# SUPPLY.net
KiCad netlist of a schematic drawn in Altium Designer
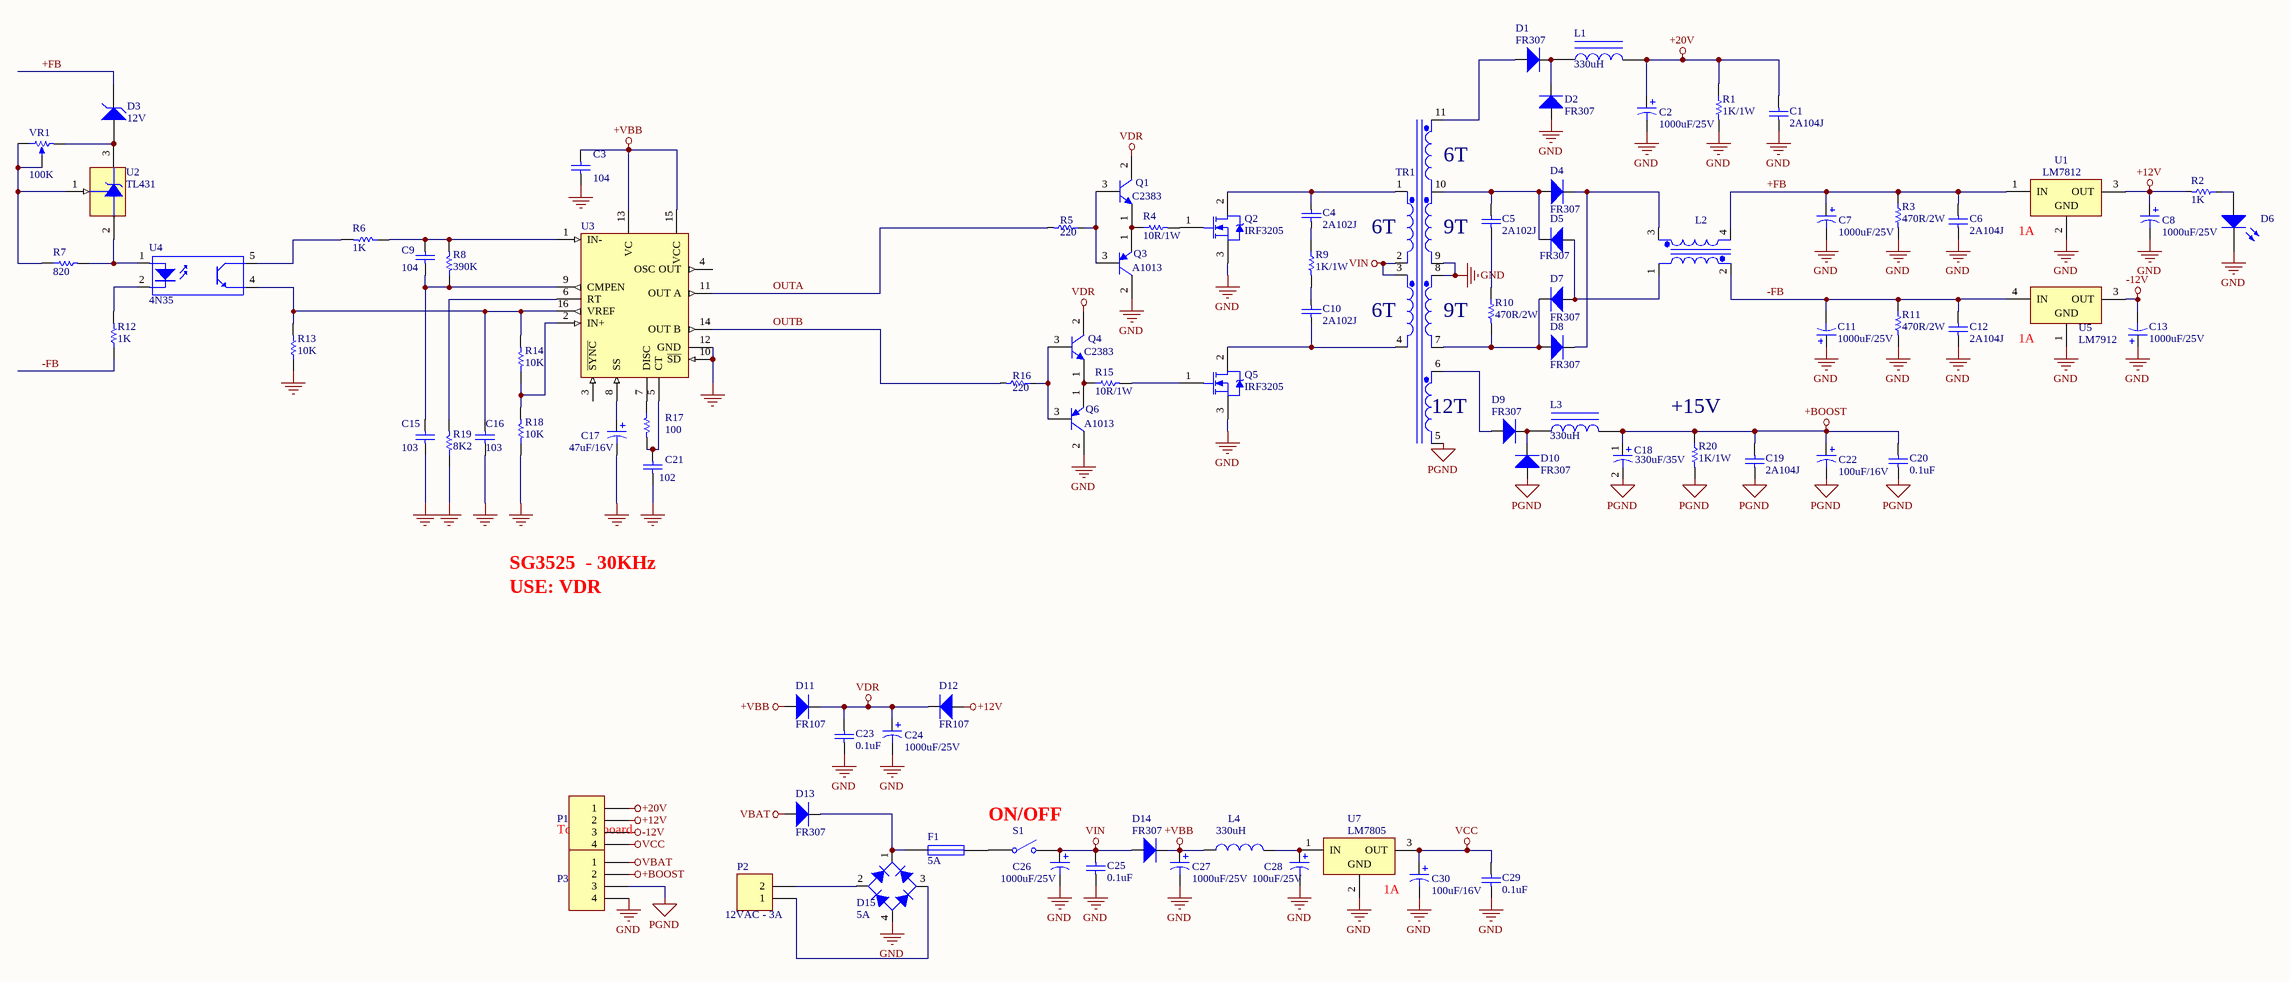
[diagram p0: SUPPLY.SchDoc]

(export (version "E")
  (design (tool "Eeschema 10.0.6"))
  (components
    (comp (ref "C1")
      (value "2A104J")
      (footprint "CAP2/3")
      (description "Capacitor")
      (fields (field (name "PUBLISHER") "Altium Limited"))
      (libsource (lib "Miscellaneous Devices") (part "Cap"))
    )
    (comp (ref "C2")
      (value "1000uF/25V")
      (footprint "C-400")
      (description "Polarized Capacitor (Radial)")
      (fields (field (name "PUBLISHER") "Altium Limited"))
      (libsource (lib "Miscellaneous Devices") (part "Cap Pol1"))
    )
    (comp (ref "C3")
      (value "104")
      (footprint "C1206")
      (description "Capacitor")
      (fields (field (name "PUBLISHER") "Altium Limited"))
      (libsource (lib "Miscellaneous Devices") (part "Cap"))
    )
    (comp (ref "C4")
      (value "2A102J")
      (footprint "CAP200")
      (description "Capacitor")
      (fields (field (name "PUBLISHER") "Altium Limited"))
      (libsource (lib "") (part "Cap_1"))
    )
    (comp (ref "C5")
      (value "2A102J")
      (footprint "CAP200")
      (description "Capacitor")
      (fields (field (name "PUBLISHER") "Altium Limited"))
      (libsource (lib "Miscellaneous Devices") (part "Cap"))
    )
    (comp (ref "C6")
      (value "2A104J")
      (footprint "CAP2/3")
      (description "Capacitor")
      (fields (field (name "PUBLISHER") "Altium Limited"))
      (libsource (lib "Miscellaneous Devices") (part "Cap"))
    )
    (comp (ref "C7")
      (value "1000uF/25V")
      (footprint "C-400")
      (description "Polarized Capacitor (Radial)")
      (fields (field (name "PUBLISHER") "Altium Limited"))
      (libsource (lib "Miscellaneous Devices") (part "Cap Pol1"))
    )
    (comp (ref "C8")
      (value "1000uF/25V")
      (footprint "C-400")
      (description "Polarized Capacitor (Radial)")
      (fields (field (name "PUBLISHER") "Altium Limited"))
      (libsource (lib "Miscellaneous Devices") (part "Cap Pol1"))
    )
    (comp (ref "C9")
      (value "104")
      (footprint "C1206")
      (description "Capacitor")
      (fields (field (name "PUBLISHER") "Altium Limited"))
      (libsource (lib "Miscellaneous Devices") (part "Cap"))
    )
    (comp (ref "C10")
      (value "2A102J")
      (footprint "CAP200")
      (description "Capacitor")
      (fields (field (name "PUBLISHER") "Altium Limited"))
      (libsource (lib "") (part "Cap_1"))
    )
    (comp (ref "C11")
      (value "1000uF/25V")
      (footprint "C-400")
      (description "Polarized Capacitor (Radial)")
      (fields (field (name "PUBLISHER") "Altium Limited"))
      (libsource (lib "Miscellaneous Devices") (part "Cap Pol1"))
    )
    (comp (ref "C12")
      (value "2A104J")
      (footprint "CAP2/3")
      (description "Capacitor")
      (fields (field (name "PUBLISHER") "Altium Limited"))
      (libsource (lib "Miscellaneous Devices") (part "Cap"))
    )
    (comp (ref "C13")
      (value "1000uF/25V")
      (footprint "C-400")
      (description "Polarized Capacitor (Radial)")
      (fields (field (name "PUBLISHER") "Altium Limited"))
      (libsource (lib "Miscellaneous Devices") (part "Cap Pol1"))
    )
    (comp (ref "C15")
      (value "103")
      (footprint "C0805")
      (description "Capacitor")
      (fields (field (name "PUBLISHER") "Altium Limited"))
      (libsource (lib "Miscellaneous Devices") (part "Cap"))
    )
    (comp (ref "C16")
      (value "103")
      (footprint "C0805")
      (description "Capacitor")
      (fields (field (name "PUBLISHER") "Altium Limited"))
      (libsource (lib "Miscellaneous Devices") (part "Cap"))
    )
    (comp (ref "C17")
      (value "47uF/16V")
      (footprint "C107-SMD")
      (description "Polarized Capacitor (Radial)")
      (fields (field (name "PUBLISHER") "Altium Limited"))
      (libsource (lib "Miscellaneous Devices") (part "Cap Pol1"))
    )
    (comp (ref "C18")
      (value "330uF/35V")
      (footprint "CAP-100UF/63V")
      (description "Polarized Capacitor (Radial)")
      (fields (field (name "PUBLISHER") "Altium Limited"))
      (libsource (lib "") (part "Cap Pol1_1"))
    )
    (comp (ref "C19")
      (value "2A104J")
      (footprint "CAP2/3")
      (description "Capacitor")
      (fields (field (name "PUBLISHER") "Altium Limited"))
      (libsource (lib "Miscellaneous Devices") (part "Cap"))
    )
    (comp (ref "C20")
      (value "0.1uF")
      (footprint "C1206")
      (description "Capacitor")
      (fields (field (name "PUBLISHER") "Altium Limited"))
      (libsource (lib "Miscellaneous Devices") (part "Cap"))
    )
    (comp (ref "C21")
      (value "102")
      (footprint "C0805")
      (description "Capacitor")
      (fields (field (name "PUBLISHER") "Altium Limited"))
      (libsource (lib "Miscellaneous Devices") (part "Cap"))
    )
    (comp (ref "C22")
      (value "100uF/16V")
      (footprint "CAP-100UF/16V")
      (description "Polarized Capacitor (Radial)")
      (fields (field (name "PUBLISHER") "Altium Limited"))
      (libsource (lib "Miscellaneous Devices") (part "Cap Pol1"))
    )
    (comp (ref "C23")
      (value "0.1uF")
      (footprint "C1206")
      (description "Capacitor")
      (fields (field (name "PUBLISHER") "Altium Limited"))
      (libsource (lib "Miscellaneous Devices") (part "Cap"))
    )
    (comp (ref "C24")
      (value "1000uF/25V")
      (footprint "C-400")
      (description "Polarized Capacitor (Radial)")
      (fields (field (name "PUBLISHER") "Altium Limited"))
      (libsource (lib "Miscellaneous Devices") (part "Cap Pol1"))
    )
    (comp (ref "C25")
      (value "0.1uF")
      (footprint "C1206")
      (description "Capacitor")
      (fields (field (name "PUBLISHER") "Altium Limited"))
      (libsource (lib "Miscellaneous Devices") (part "Cap"))
    )
    (comp (ref "C26")
      (value "1000uF/25V")
      (footprint "C-400")
      (description "Polarized Capacitor (Radial)")
      (fields (field (name "PUBLISHER") "Altium Limited"))
      (libsource (lib "Miscellaneous Devices") (part "Cap Pol1"))
    )
    (comp (ref "C27")
      (value "1000uF/25V")
      (footprint "C-400")
      (description "Polarized Capacitor (Radial)")
      (fields (field (name "PUBLISHER") "Altium Limited"))
      (libsource (lib "Miscellaneous Devices") (part "Cap Pol1"))
    )
    (comp (ref "C28")
      (value "100uF/25V")
      (footprint "CAP-100UF/16V")
      (description "Polarized Capacitor (Radial)")
      (fields (field (name "Comment") "100uF") (field (name "PUBLISHER") "Altium Limited"))
      (libsource (lib "Miscellaneous Devices") (part "Cap Pol1"))
    )
    (comp (ref "C29")
      (value "0.1uF")
      (footprint "C1206")
      (description "Capacitor")
      (fields (field (name "PUBLISHER") "Altium Limited"))
      (libsource (lib "Miscellaneous Devices") (part "Cap"))
    )
    (comp (ref "C30")
      (value "100uF/16V")
      (footprint "CAP-100UF/16V")
      (description "Polarized Capacitor (Radial)")
      (fields (field (name "PUBLISHER") "Altium Limited"))
      (libsource (lib "Miscellaneous Devices") (part "Cap Pol1"))
    )
    (comp (ref "D1")
      (value "FR307")
      (footprint "FR307")
      (description "High Conductance Fast Diode")
      (fields (field (name "PUBLISHER") "Altium Limited"))
      (libsource (lib "Miscellaneous Devices") (part "Diode 1N4148"))
    )
    (comp (ref "D2")
      (value "FR307")
      (footprint "FR307")
      (description "High Conductance Fast Diode")
      (fields (field (name "PUBLISHER") "Altium Limited"))
      (libsource (lib "Miscellaneous Devices") (part "Diode 1N4148"))
    )
    (comp (ref "D3")
      (value "12V")
      (footprint "1N4148")
      (description "Zener Diode")
      (fields (field (name "PUBLISHER") "Altium Limited"))
      (libsource (lib "Miscellaneous Devices") (part "D Zener"))
    )
    (comp (ref "D4")
      (value "FR307")
      (footprint "FR307")
      (description "High Conductance Fast Diode")
      (fields (field (name "PUBLISHER") "Altium Limited"))
      (libsource (lib "Miscellaneous Devices") (part "Diode 1N4148"))
    )
    (comp (ref "D5")
      (value "FR307")
      (footprint "FR307")
      (description "High Conductance Fast Diode")
      (fields (field (name "PUBLISHER") "Altium Limited"))
      (libsource (lib "Miscellaneous Devices") (part "Diode 1N4148"))
    )
    (comp (ref "D6")
      (value "LED")
      (footprint "LED-1206/100x100")
      (description "Typical INFRARED GaAs LED")
      (fields (field (name "PUBLISHER") "Altium Limited"))
      (libsource (lib "Miscellaneous Devices") (part "LED0"))
    )
    (comp (ref "D7")
      (value "FR307")
      (footprint "FR307")
      (description "High Conductance Fast Diode")
      (fields (field (name "PUBLISHER") "Altium Limited"))
      (libsource (lib "Miscellaneous Devices") (part "Diode 1N4148"))
    )
    (comp (ref "D8")
      (value "FR307")
      (footprint "FR307")
      (description "High Conductance Fast Diode")
      (fields (field (name "PUBLISHER") "Altium Limited"))
      (libsource (lib "Miscellaneous Devices") (part "Diode 1N4148"))
    )
    (comp (ref "D9")
      (value "FR307")
      (footprint "FR307")
      (description "High Conductance Fast Diode")
      (fields (field (name "PUBLISHER") "Altium Limited"))
      (libsource (lib "Miscellaneous Devices") (part "Diode 1N4148"))
    )
    (comp (ref "D10")
      (value "FR307")
      (footprint "FR307")
      (description "High Conductance Fast Diode")
      (fields (field (name "PUBLISHER") "Altium Limited"))
      (libsource (lib "Miscellaneous Devices") (part "Diode 1N4148"))
    )
    (comp (ref "D11")
      (value "FR107")
      (footprint "DIODE-1A/150")
      (description "High Conductance Fast Diode")
      (fields (field (name "PUBLISHER") "Altium Limited"))
      (libsource (lib "Miscellaneous Devices") (part "Diode 1N4148"))
    )
    (comp (ref "D12")
      (value "FR107")
      (footprint "DIODE-1A/300")
      (description "High Conductance Fast Diode")
      (fields (field (name "PUBLISHER") "Altium Limited"))
      (libsource (lib "Miscellaneous Devices") (part "Diode 1N4148"))
    )
    (comp (ref "D13")
      (value "FR307")
      (footprint "FR307")
      (description "High Conductance Fast Diode")
      (fields (field (name "PUBLISHER") "Altium Limited"))
      (libsource (lib "Miscellaneous Devices") (part "Diode 1N4148"))
    )
    (comp (ref "D14")
      (value "FR307")
      (footprint "FR307")
      (description "High Conductance Fast Diode")
      (fields (field (name "PUBLISHER") "Altium Limited"))
      (libsource (lib "Miscellaneous Devices") (part "Diode 1N4148"))
    )
    (comp (ref "D15")
      (value "5A")
      (footprint "DB-5A")
      (description "Full Wave Diode Bridge")
      (fields (field (name "PUBLISHER") "Altium Limited"))
      (libsource (lib "Miscellaneous Devices") (part "Bridge1"))
    )
    (comp (ref "F1")
      (value "5A")
      (footprint "FUSE-AC")
      (description "Fuse")
      (fields (field (name "PUBLISHER") "Altium Limited"))
      (libsource (lib "Miscellaneous Devices") (part "Fuse 1"))
    )
    (comp (ref "L1")
      (value "330uH")
      (footprint "L-330uH")
      (description "Magnetic-Core Inductor")
      (fields (field (name "MANUFACTURER") "Generic Components"))
      (libsource (lib "Miscellaneous Devices") (part "Inductor Iron"))
    )
    (comp (ref "L2")
      (value "Trans Cupl")
      (footprint "IDN-FILTER")
      (description "Transformer (Coupled Inductor Model)")
      (fields (field (name "PUBLISHER") "Altium Limited"))
      (libsource (lib "Miscellaneous Devices") (part "Trans Cupl"))
    )
    (comp (ref "L3")
      (value "330uH")
      (footprint "L-330uH")
      (description "Magnetic-Core Inductor")
      (fields (field (name "MANUFACTURER") "Generic Components"))
      (libsource (lib "Miscellaneous Devices") (part "Inductor Iron"))
    )
    (comp (ref "L4")
      (value "330uH")
      (footprint "L-330uH")
      (description "Inductor")
      (fields (field (name "PUBLISHER") "Altium Limited"))
      (libsource (lib "Miscellaneous Devices") (part "Inductor"))
    )
    (comp (ref "P1")
      (value "Header 4")
      (footprint "H4-15A")
      (description "Header, 4-Pin")
      (fields (field (name "PUBLISHER") "Altium Limited"))
      (libsource (lib "Miscellaneous Connectors") (part "Header 4"))
    )
    (comp (ref "P2")
      (value "Header 2")
      (footprint "H2-15A")
      (description "Header, 2-Pin")
      (fields (field (name "PUBLISHER") "Altium Limited"))
      (libsource (lib "Miscellaneous Connectors") (part "Header 2"))
    )
    (comp (ref "P3")
      (value "Header 4")
      (footprint "H4-15A")
      (description "Header, 4-Pin")
      (fields (field (name "PUBLISHER") "Altium Limited"))
      (libsource (lib "Miscellaneous Connectors") (part "Header 4"))
    )
    (comp (ref "Q1")
      (value "C2383")
      (footprint "TO-92")
      (description "NPN General Purpose Amplifier")
      (fields (field (name "PUBLISHER") "Altium Limited"))
      (libsource (lib "Miscellaneous Devices") (part "2N3904"))
    )
    (comp (ref "Q2")
      (value "IRF3205")
      (footprint "TO-220HSN")
      (description "HEXFET Power MOSFET")
      (fields (field (name "PUBLISHER") "Altium Limited"))
      (libsource (lib "IR Discrete MOSFET - Power") (part "IRF3205"))
    )
    (comp (ref "Q3")
      (value "A1013")
      (footprint "TO-92")
      (description "PNP General Purpose Amplifier")
      (fields
        (field (name "MANUFACTURER") "Generic Components")
        (field (name "PUBLISHER") "Altium Hobart Technology Centre")
      )
      (libsource (lib "Miscellaneous Devices") (part "2N3906"))
    )
    (comp (ref "Q4")
      (value "C2383")
      (footprint "TO-92")
      (description "NPN General Purpose Amplifier")
      (fields (field (name "PUBLISHER") "Altium Limited"))
      (libsource (lib "Miscellaneous Devices") (part "2N3904"))
    )
    (comp (ref "Q5")
      (value "IRF3205")
      (footprint "TO-220HSN")
      (description "HEXFET Power MOSFET")
      (fields (field (name "PUBLISHER") "Altium Limited"))
      (libsource (lib "IR Discrete MOSFET - Power") (part "IRF3205"))
    )
    (comp (ref "Q6")
      (value "A1013")
      (footprint "TO-92")
      (description "PNP General Purpose Amplifier")
      (fields
        (field (name "MANUFACTURER") "Generic Components")
        (field (name "PUBLISHER") "Altium Hobart Technology Centre")
      )
      (libsource (lib "Miscellaneous Devices") (part "2N3906"))
    )
    (comp (ref "R1")
      (value "1K/1W")
      (footprint "RES-500")
      (description "Resistor")
      (fields (field (name "PUBLISHER") "Altium Limited"))
      (libsource (lib "Miscellaneous Devices") (part "Res1"))
    )
    (comp (ref "R2")
      (value "1K")
      (footprint "R1206")
      (description "Resistor")
      (fields (field (name "PUBLISHER") "Altium Limited"))
      (libsource (lib "") (part "Res1_2"))
    )
    (comp (ref "R3")
      (value "470R/2W")
      (footprint "RES-2W/200")
      (description "Resistor")
      (fields (field (name "PUBLISHER") "Altium Limited"))
      (libsource (lib "Miscellaneous Devices") (part "Res1"))
    )
    (comp (ref "R4")
      (value "10R/1W")
      (footprint "RES-500")
      (description "Resistor")
      (fields (field (name "PUBLISHER") "Altium Limited"))
      (libsource (lib "Miscellaneous Devices") (part "Res1"))
    )
    (comp (ref "R5")
      (value "220")
      (footprint "R0805")
      (description "Resistor")
      (fields (field (name "PUBLISHER") "Altium Limited"))
      (libsource (lib "") (part "Res1_2"))
    )
    (comp (ref "R6")
      (value "1K")
      (footprint "R0805")
      (description "Resistor")
      (fields (field (name "PUBLISHER") "Altium Limited"))
      (libsource (lib "") (part "Res1_1"))
    )
    (comp (ref "R7")
      (value "820")
      (footprint "R0805")
      (description "Resistor")
      (fields (field (name "PUBLISHER") "Altium Limited"))
      (libsource (lib "") (part "Res1_1"))
    )
    (comp (ref "R8")
      (value "390K")
      (footprint "R0805")
      (description "Resistor")
      (fields (field (name "PUBLISHER") "Altium Limited"))
      (libsource (lib "Miscellaneous Devices") (part "Res1"))
    )
    (comp (ref "R9")
      (value "1K/1W")
      (footprint "RES-1W/110")
      (description "Resistor")
      (fields (field (name "PUBLISHER") "Altium Limited"))
      (libsource (lib "Miscellaneous Devices") (part "Res1"))
    )
    (comp (ref "R10")
      (value "470R/2W")
      (footprint "RES-2W/200")
      (description "Resistor")
      (fields (field (name "PUBLISHER") "Altium Limited"))
      (libsource (lib "Miscellaneous Devices") (part "Res1"))
    )
    (comp (ref "R11")
      (value "470R/2W")
      (footprint "RES-2W/200")
      (description "Resistor")
      (fields (field (name "PUBLISHER") "Altium Limited"))
      (libsource (lib "Miscellaneous Devices") (part "Res1"))
    )
    (comp (ref "R12")
      (value "1K")
      (footprint "R1206")
      (description "Resistor")
      (fields (field (name "PUBLISHER") "Altium Limited"))
      (libsource (lib "Miscellaneous Devices") (part "Res1"))
    )
    (comp (ref "R13")
      (value "10K")
      (footprint "R0805")
      (description "Resistor")
      (fields (field (name "PUBLISHER") "Altium Limited"))
      (libsource (lib "Miscellaneous Devices") (part "Res1"))
    )
    (comp (ref "R14")
      (value "10K")
      (footprint "R0805")
      (description "Resistor")
      (fields (field (name "PUBLISHER") "Altium Limited"))
      (libsource (lib "Miscellaneous Devices") (part "Res1"))
    )
    (comp (ref "R15")
      (value "10R/1W")
      (footprint "RES-500")
      (description "Resistor")
      (fields (field (name "PUBLISHER") "Altium Limited"))
      (libsource (lib "Miscellaneous Devices") (part "Res1"))
    )
    (comp (ref "R16")
      (value "220")
      (footprint "R0805")
      (description "Resistor")
      (fields (field (name "PUBLISHER") "Altium Limited"))
      (libsource (lib "") (part "Res1_2"))
    )
    (comp (ref "R17")
      (value "100")
      (footprint "R0805")
      (description "Resistor")
      (fields (field (name "PUBLISHER") "Altium Limited"))
      (libsource (lib "Miscellaneous Devices") (part "Res1"))
    )
    (comp (ref "R18")
      (value "10K")
      (footprint "R0805")
      (description "Resistor")
      (fields (field (name "PUBLISHER") "Altium Limited"))
      (libsource (lib "Miscellaneous Devices") (part "Res1"))
    )
    (comp (ref "R19")
      (value "8K2")
      (footprint "R0805")
      (description "Resistor")
      (fields (field (name "PUBLISHER") "Altium Limited"))
      (libsource (lib "Miscellaneous Devices") (part "Res1"))
    )
    (comp (ref "R20")
      (value "1K/1W")
      (footprint "RES-500")
      (description "Resistor")
      (fields (field (name "PUBLISHER") "Altium Limited"))
      (libsource (lib "Miscellaneous Devices") (part "Res1"))
    )
    (comp (ref "S1")
      (value "SW-SPST")
      (footprint "H2-15A")
      (description "Single-Pole, Single-Throw Switch")
      (fields (field (name "PUBLISHER") "Altium Limited"))
      (libsource (lib "Miscellaneous Devices") (part "SW-SPST"))
    )
    (comp (ref "TR1")
      (value "TR3/5")
      (footprint "TRANS3/5")
      (description "Transformer power supply for accu recovery")
      (libsource (lib "Recovery") (part "TRANS3/5"))
    )
    (comp (ref "U1")
      (value "LM7812")
      (footprint "Library:DDPAK/TO-263 (KTT)")
      (description "3-Terminal Positive Fixed Voltage Regulator")
      (fields (field (name "PUBLISHER") "Altium Limited"))
      (libsource (lib "Motorola Power Mgt Voltage Regulator") (part "MC7805CT"))
    )
    (comp (ref "U2")
      (value "TL431")
      (footprint "TO-92")
      (description "Programmable Precision Reference")
      (fields (field (name "PUBLISHER") "Altium Limited"))
      (libsource (lib "Motorola Power Mgt Voltage Reference") (part "TL431ACLP"))
    )
    (comp (ref "U3")
      (value "SG3525AN")
      (footprint "648-06")
      (description "Pulse Width Modulator Control Circuit")
      (fields (field (name "PUBLISHER") "Altium Limited"))
      (libsource (lib "Motorola Power Mgt SMPS Controller") (part "SG3525AN"))
    )
    (comp (ref "U4") (value "4N35") (footprint "DIP-6/300") (libsource (lib "Library") (part "4N35")))
    (comp (ref "U5")
      (value "LM7912")
      (footprint "DDPAK/TO-263 (KTT)")
      (description "IC REG NEG VOLT 12V D2PAK")
      (fields (field (name "PART NUMBER") "L7912CD2T-TR") (field (name "MANUFACTURER") "STMicroelectronics"))
      (libsource (lib "ST Power Mgt Voltage Regulator") (part "L7912CD2T"))
    )
    (comp (ref "U7")
      (value "LM7805")
      (footprint "DDPAK/TO-263 (KTT)")
      (description "3-Terminal Positive Fixed Voltage Regulator")
      (fields (field (name "PUBLISHER") "Altium Limited"))
      (libsource (lib "Motorola Power Mgt Voltage Regulator") (part "MC7805CT"))
    )
    (comp (ref "VR1")
      (value "100K")
      (footprint "VR-S")
      (description "Potentiometer")
      (fields (field (name "PUBLISHER") "Altium Limited"))
      (libsource (lib "Miscellaneous Devices") (part "RPot"))
    )
  )
  (nets
    (net (code "1") (name "+12V") (class "Default")
      (node (ref "C8") (pin "1") (pinfunction "1_1") (pintype "passive"))
      (node (ref "D12") (pin "1") (pinfunction "A_1") (pintype "passive"))
      (node (ref "P1") (pin "2") (pinfunction "2_2") (pintype "passive"))
      (node (ref "R2") (pin "2") (pinfunction "2_2") (pintype "passive"))
      (node (ref "U1") (pin "3") (pinfunction "OUT_3") (pintype "power_in"))
    )
    (net (code "2") (name "+20V") (class "Default")
      (node (ref "C1") (pin "2") (pinfunction "2_2") (pintype "passive"))
      (node (ref "C2") (pin "1") (pinfunction "1_1") (pintype "passive"))
      (node (ref "L1") (pin "2") (pinfunction "2_2") (pintype "passive"))
      (node (ref "P1") (pin "1") (pinfunction "1_1") (pintype "passive"))
      (node (ref "R1") (pin "1") (pinfunction "1_1") (pintype "passive"))
    )
    (net (code "3") (name "+BOOST") (class "Default")
      (node (ref "C18") (pin "1") (pinfunction "1_1") (pintype "passive"))
      (node (ref "C19") (pin "2") (pinfunction "2_2") (pintype "passive"))
      (node (ref "C20") (pin "1") (pinfunction "1_1") (pintype "passive"))
      (node (ref "C22") (pin "1") (pinfunction "1_1") (pintype "passive"))
      (node (ref "L3") (pin "2") (pinfunction "2_2") (pintype "passive"))
      (node (ref "P3") (pin "2") (pinfunction "2_2") (pintype "passive"))
      (node (ref "R20") (pin "1") (pinfunction "1_1") (pintype "passive"))
    )
    (net (code "4") (name "+VBB") (class "Default")
      (node (ref "C27") (pin "1") (pinfunction "1_1") (pintype "passive"))
      (node (ref "C3") (pin "2") (pinfunction "2_2") (pintype "passive"))
      (node (ref "D11") (pin "1") (pinfunction "A_1") (pintype "passive"))
      (node (ref "D14") (pin "2") (pinfunction "K_2") (pintype "passive"))
      (node (ref "L4") (pin "1") (pinfunction "1_1") (pintype "passive"))
      (node (ref "U3") (pin "13") (pinfunction "VC_13") (pintype "power_in"))
      (node (ref "U3") (pin "15") (pinfunction "VCC_15") (pintype "power_in"))
    )
    (net (code "5") (name "-12V") (class "Default")
      (node (ref "C13") (pin "2") (pinfunction "2_2") (pintype "passive"))
      (node (ref "P1") (pin "3") (pinfunction "3_3") (pintype "passive"))
      (node (ref "U5") (pin "3") (pinfunction "OUT_3") (pintype "power_in"))
    )
    (net (code "6") (name "/+FB") (class "Default")
      (node (ref "C6") (pin "1") (pinfunction "1_1") (pintype "passive"))
      (node (ref "C7") (pin "1") (pinfunction "1_1") (pintype "passive"))
      (node (ref "D3") (pin "2") (pinfunction "K_2") (pintype "passive"))
      (node (ref "L2") (pin "4") (pinfunction "Sec-_4") (pintype "passive"))
      (node (ref "R3") (pin "1") (pinfunction "1_1") (pintype "passive"))
      (node (ref "U1") (pin "1") (pinfunction "IN_1") (pintype "power_in"))
    )
    (net (code "7") (name "/-FB") (class "Default")
      (node (ref "C11") (pin "2") (pinfunction "2_2") (pintype "passive"))
      (node (ref "C12") (pin "2") (pinfunction "2_2") (pintype "passive"))
      (node (ref "L2") (pin "2") (pinfunction "Pri-_2") (pintype "passive"))
      (node (ref "R11") (pin "1") (pinfunction "1_1") (pintype "passive"))
      (node (ref "R12") (pin "1") (pinfunction "1_1") (pintype "passive"))
      (node (ref "U5") (pin "4") (pinfunction "IN_4") (pintype "power_in"))
    )
    (net (code "8") (name "/OUTA") (class "Default")
      (node (ref "R5") (pin "2") (pinfunction "2_2") (pintype "passive"))
      (node (ref "U3") (pin "11") (pinfunction "OUT_A_11") (pintype "output"))
    )
    (net (code "9") (name "/OUTB") (class "Default")
      (node (ref "R16") (pin "2") (pinfunction "2_2") (pintype "passive"))
      (node (ref "U3") (pin "14") (pinfunction "OUT_B_14") (pintype "output"))
    )
    (net (code "10") (name "GND") (class "Default")
      (node (ref "C1") (pin "1") (pinfunction "1_1") (pintype "passive"))
      (node (ref "C11") (pin "1") (pinfunction "1_1") (pintype "passive"))
      (node (ref "C12") (pin "1") (pinfunction "1_1") (pintype "passive"))
      (node (ref "C13") (pin "1") (pinfunction "1_1") (pintype "passive"))
      (node (ref "C15") (pin "1") (pinfunction "1_1") (pintype "passive"))
      (node (ref "C16") (pin "1") (pinfunction "1_1") (pintype "passive"))
      (node (ref "C17") (pin "2") (pinfunction "2_2") (pintype "passive"))
      (node (ref "C2") (pin "2") (pinfunction "2_2") (pintype "passive"))
      (node (ref "C21") (pin "1") (pinfunction "1_1") (pintype "passive"))
      (node (ref "C23") (pin "2") (pinfunction "2_2") (pintype "passive"))
      (node (ref "C24") (pin "2") (pinfunction "2_2") (pintype "passive"))
      (node (ref "C25") (pin "2") (pinfunction "2_2") (pintype "passive"))
      (node (ref "C26") (pin "2") (pinfunction "2_2") (pintype "passive"))
      (node (ref "C27") (pin "2") (pinfunction "2_2") (pintype "passive"))
      (node (ref "C28") (pin "2") (pinfunction "2_2") (pintype "passive"))
      (node (ref "C29") (pin "2") (pinfunction "2_2") (pintype "passive"))
      (node (ref "C3") (pin "1") (pinfunction "1_1") (pintype "passive"))
      (node (ref "C30") (pin "2") (pinfunction "2_2") (pintype "passive"))
      (node (ref "C6") (pin "2") (pinfunction "2_2") (pintype "passive"))
      (node (ref "C7") (pin "2") (pinfunction "2_2") (pintype "passive"))
      (node (ref "C8") (pin "2") (pinfunction "2_2") (pintype "passive"))
      (node (ref "D15") (pin "4") (pinfunction "A_4") (pintype "passive"))
      (node (ref "D2") (pin "1") (pinfunction "A_1") (pintype "passive"))
      (node (ref "D6") (pin "2") (pinfunction "K_2") (pintype "passive"))
      (node (ref "P3") (pin "4") (pinfunction "4_4") (pintype "passive"))
      (node (ref "Q2") (pin "3") (pinfunction "S_3") (pintype "passive"))
      (node (ref "Q3") (pin "2") (pinfunction "C_2") (pintype "passive"))
      (node (ref "Q5") (pin "3") (pinfunction "S_3") (pintype "passive"))
      (node (ref "Q6") (pin "2") (pinfunction "C_2") (pintype "passive"))
      (node (ref "R1") (pin "2") (pinfunction "2_2") (pintype "passive"))
      (node (ref "R11") (pin "2") (pinfunction "2_2") (pintype "passive"))
      (node (ref "R13") (pin "1") (pinfunction "1_1") (pintype "passive"))
      (node (ref "R18") (pin "1") (pinfunction "1_1") (pintype "passive"))
      (node (ref "R19") (pin "1") (pinfunction "1_1") (pintype "passive"))
      (node (ref "R3") (pin "2") (pinfunction "2_2") (pintype "passive"))
      (node (ref "TR1") (pin "8") (pinfunction "Sec2+_8") (pintype "passive"))
      (node (ref "TR1") (pin "9") (pinfunction "Sec1-_9") (pintype "passive"))
      (node (ref "U1") (pin "2") (pinfunction "GND_2") (pintype "power_in"))
      (node (ref "U3") (pin "10") (pinfunction "~{SD}_10") (pintype "input"))
      (node (ref "U3") (pin "12") (pinfunction "GND_12") (pintype "power_in"))
      (node (ref "U5") (pin "1") (pinfunction "GND_1") (pintype "power_in"))
      (node (ref "U7") (pin "2") (pinfunction "GND_2") (pintype "power_in"))
    )
    (net (code "11") (name "Net-(C4-Pad1)") (class "Default")
      (node (ref "C4") (pin "1") (pinfunction "1_1") (pintype "passive"))
      (node (ref "R9") (pin "1") (pinfunction "1_1") (pintype "passive"))
    )
    (net (code "12") (name "Net-(C5-Pad1)") (class "Default")
      (node (ref "C5") (pin "1") (pinfunction "1_1") (pintype "passive"))
      (node (ref "R10") (pin "1") (pinfunction "1_1") (pintype "passive"))
    )
    (net (code "13") (name "Net-(C10-Pad2)") (class "Default")
      (node (ref "C10") (pin "2") (pinfunction "2_2") (pintype "passive"))
      (node (ref "R9") (pin "2") (pinfunction "2_2") (pintype "passive"))
    )
    (net (code "14") (name "Net-(D1-A)") (class "Default")
      (node (ref "D1") (pin "1") (pinfunction "A_1") (pintype "passive"))
      (node (ref "TR1") (pin "11") (pinfunction "Sec4_11") (pintype "passive"))
    )
    (net (code "15") (name "Net-(D1-K)") (class "Default")
      (node (ref "D1") (pin "2") (pinfunction "K_2") (pintype "passive"))
      (node (ref "D2") (pin "2") (pinfunction "K_2") (pintype "passive"))
      (node (ref "L1") (pin "1") (pinfunction "1_1") (pintype "passive"))
    )
    (net (code "16") (name "Net-(D3-A)") (class "Default")
      (node (ref "D3") (pin "1") (pinfunction "A_1") (pintype "passive"))
      (node (ref "U2") (pin "3") (pinfunction "K_3") (pintype "passive"))
      (node (ref "VR1") (pin "2") (pinfunction "BOT_2") (pintype "passive"))
    )
    (net (code "17") (name "Net-(D4-A)") (class "Default")
      (node (ref "C5") (pin "2") (pinfunction "2_2") (pintype "passive"))
      (node (ref "D4") (pin "1") (pinfunction "A_1") (pintype "passive"))
      (node (ref "D5") (pin "2") (pinfunction "K_2") (pintype "passive"))
      (node (ref "TR1") (pin "10") (pinfunction "Sec1+_10") (pintype "passive"))
    )
    (net (code "18") (name "Net-(D4-K)") (class "Default")
      (node (ref "D4") (pin "2") (pinfunction "K_2") (pintype "passive"))
      (node (ref "D8") (pin "2") (pinfunction "K_2") (pintype "passive"))
      (node (ref "L2") (pin "3") (pinfunction "Sec+_3") (pintype "passive"))
    )
    (net (code "19") (name "Net-(D5-A)") (class "Default")
      (node (ref "D5") (pin "1") (pinfunction "A_1") (pintype "passive"))
      (node (ref "D7") (pin "1") (pinfunction "A_1") (pintype "passive"))
      (node (ref "L2") (pin "1") (pinfunction "Pri+_1") (pintype "passive"))
    )
    (net (code "20") (name "Net-(D6-A)") (class "Default")
      (node (ref "D6") (pin "1") (pinfunction "A_1") (pintype "passive"))
      (node (ref "R2") (pin "1") (pinfunction "1_1") (pintype "passive"))
    )
    (net (code "21") (name "Net-(D7-K)") (class "Default")
      (node (ref "D7") (pin "2") (pinfunction "K_2") (pintype "passive"))
      (node (ref "D8") (pin "1") (pinfunction "A_1") (pintype "passive"))
      (node (ref "R10") (pin "2") (pinfunction "2_2") (pintype "passive"))
      (node (ref "TR1") (pin "7") (pinfunction "Sec2-_7") (pintype "passive"))
    )
    (net (code "22") (name "Net-(D9-A)") (class "Default")
      (node (ref "D9") (pin "1") (pinfunction "A_1") (pintype "passive"))
      (node (ref "TR1") (pin "6") (pinfunction "Sec3+_6") (pintype "passive"))
    )
    (net (code "23") (name "Net-(D10-K)") (class "Default")
      (node (ref "D10") (pin "2") (pinfunction "K_2") (pintype "passive"))
      (node (ref "D9") (pin "2") (pinfunction "K_2") (pintype "passive"))
      (node (ref "L3") (pin "1") (pinfunction "1_1") (pintype "passive"))
    )
    (net (code "24") (name "Net-(D13-K)") (class "Default")
      (node (ref "D13") (pin "2") (pinfunction "K_2") (pintype "passive"))
      (node (ref "D15") (pin "1") (pinfunction "K_1") (pintype "passive"))
      (node (ref "F1") (pin "2") (pinfunction "2_2") (pintype "passive"))
    )
    (net (code "25") (name "Net-(D15-C-Pad2)") (class "Default")
      (node (ref "D15") (pin "2") (pinfunction "C_2") (pintype "passive"))
      (node (ref "P2") (pin "2") (pinfunction "2_2") (pintype "passive"))
    )
    (net (code "26") (name "Net-(D15-C-Pad3)") (class "Default")
      (node (ref "D15") (pin "3") (pinfunction "C_3") (pintype "passive"))
      (node (ref "P2") (pin "1") (pinfunction "1_1") (pintype "passive"))
    )
    (net (code "27") (name "Net-(Q1-B)") (class "Default")
      (node (ref "Q1") (pin "3") (pinfunction "B_3") (pintype "passive"))
      (node (ref "Q3") (pin "3") (pinfunction "B_3") (pintype "passive"))
      (node (ref "R5") (pin "1") (pinfunction "1_1") (pintype "passive"))
    )
    (net (code "28") (name "Net-(Q1-E)") (class "Default")
      (node (ref "Q1") (pin "1") (pinfunction "E_1") (pintype "passive"))
      (node (ref "Q3") (pin "1") (pinfunction "E_1") (pintype "passive"))
      (node (ref "R4") (pin "1") (pinfunction "1_1") (pintype "passive"))
    )
    (net (code "29") (name "Net-(Q2-D)") (class "Default")
      (node (ref "C4") (pin "2") (pinfunction "2_2") (pintype "passive"))
      (node (ref "Q2") (pin "2") (pinfunction "D_2") (pintype "passive"))
      (node (ref "TR1") (pin "1") (pinfunction "Pri1+_1") (pintype "passive"))
    )
    (net (code "30") (name "Net-(Q2-G)") (class "Default")
      (node (ref "Q2") (pin "1") (pinfunction "G_1") (pintype "passive"))
      (node (ref "R4") (pin "2") (pinfunction "2_2") (pintype "passive"))
    )
    (net (code "31") (name "Net-(Q4-B)") (class "Default")
      (node (ref "Q4") (pin "3") (pinfunction "B_3") (pintype "passive"))
      (node (ref "Q6") (pin "3") (pinfunction "B_3") (pintype "passive"))
      (node (ref "R16") (pin "1") (pinfunction "1_1") (pintype "passive"))
    )
    (net (code "32") (name "Net-(Q4-E)") (class "Default")
      (node (ref "Q4") (pin "1") (pinfunction "E_1") (pintype "passive"))
      (node (ref "Q6") (pin "1") (pinfunction "E_1") (pintype "passive"))
      (node (ref "R15") (pin "1") (pinfunction "1_1") (pintype "passive"))
    )
    (net (code "33") (name "Net-(Q5-D)") (class "Default")
      (node (ref "C10") (pin "1") (pinfunction "1_1") (pintype "passive"))
      (node (ref "Q5") (pin "2") (pinfunction "D_2") (pintype "passive"))
      (node (ref "TR1") (pin "4") (pinfunction "Pri2-_4") (pintype "passive"))
    )
    (net (code "34") (name "Net-(Q5-G)") (class "Default")
      (node (ref "Q5") (pin "1") (pinfunction "G_1") (pintype "passive"))
      (node (ref "R15") (pin "2") (pinfunction "2_2") (pintype "passive"))
    )
    (net (code "35") (name "Net-(S1-COMMON)") (class "Default")
      (node (ref "F1") (pin "1") (pinfunction "1_1") (pintype "passive"))
      (node (ref "S1") (pin "1") (pinfunction "COMMON_1") (pintype "passive"))
    )
    (net (code "36") (name "Net-(U2-A)") (class "Default")
      (node (ref "R7") (pin "2") (pinfunction "2_2") (pintype "passive"))
      (node (ref "U2") (pin "2") (pinfunction "A_2") (pintype "passive"))
      (node (ref "U4") (pin "1") (pinfunction "A_1") (pintype "passive"))
    )
    (net (code "37") (name "Net-(U2-REF)") (class "Default")
      (node (ref "R7") (pin "1") (pinfunction "1_1") (pintype "passive"))
      (node (ref "U2") (pin "1") (pinfunction "REF_1") (pintype "input"))
      (node (ref "VR1") (pin "1") (pinfunction "TOP_1") (pintype "passive"))
      (node (ref "VR1") (pin "3") (pinfunction "TAP_3") (pintype "passive"))
    )
    (net (code "38") (name "Net-(U3-CMPEN)") (class "Default")
      (node (ref "C15") (pin "2") (pinfunction "2_2") (pintype "passive"))
      (node (ref "C9") (pin "1") (pinfunction "1_1") (pintype "passive"))
      (node (ref "R8") (pin "1") (pinfunction "1_1") (pintype "passive"))
      (node (ref "U3") (pin "9") (pinfunction "CMPEN_9") (pintype "output"))
    )
    (net (code "39") (name "Net-(U3-CT)") (class "Default")
      (node (ref "C21") (pin "2") (pinfunction "2_2") (pintype "passive"))
      (node (ref "R17") (pin "2") (pinfunction "2_2") (pintype "passive"))
      (node (ref "U3") (pin "5") (pinfunction "CT_5") (pintype "passive"))
    )
    (net (code "40") (name "Net-(U3-DISC)") (class "Default")
      (node (ref "R17") (pin "1") (pinfunction "1_1") (pintype "passive"))
      (node (ref "U3") (pin "7") (pinfunction "DISC_7") (pintype "open_collector"))
    )
    (net (code "41") (name "Net-(U3-IN+)") (class "Default")
      (node (ref "R14") (pin "1") (pinfunction "1_1") (pintype "passive"))
      (node (ref "R18") (pin "2") (pinfunction "2_2") (pintype "passive"))
      (node (ref "U3") (pin "2") (pinfunction "IN+_2") (pintype "input"))
    )
    (net (code "42") (name "Net-(U3-IN-)") (class "Default")
      (node (ref "C9") (pin "2") (pinfunction "2_2") (pintype "passive"))
      (node (ref "R6") (pin "1") (pinfunction "1_1") (pintype "passive"))
      (node (ref "R8") (pin "2") (pinfunction "2_2") (pintype "passive"))
      (node (ref "U3") (pin "1") (pinfunction "IN-_1") (pintype "input"))
    )
    (net (code "43") (name "Net-(U3-RT)") (class "Default")
      (node (ref "R19") (pin "2") (pinfunction "2_2") (pintype "passive"))
      (node (ref "U3") (pin "6") (pinfunction "RT_6") (pintype "passive"))
    )
    (net (code "44") (name "Net-(U3-SS)") (class "Default")
      (node (ref "C17") (pin "1") (pinfunction "1_1") (pintype "passive"))
      (node (ref "U3") (pin "8") (pinfunction "SS_8") (pintype "input"))
    )
    (net (code "45") (name "Net-(U3-VREF)") (class "Default")
      (node (ref "C16") (pin "2") (pinfunction "2_2") (pintype "passive"))
      (node (ref "R13") (pin "2") (pinfunction "2_2") (pintype "passive"))
      (node (ref "R14") (pin "2") (pinfunction "2_2") (pintype "passive"))
      (node (ref "U3") (pin "16") (pinfunction "VREF_16") (pintype "output"))
      (node (ref "U4") (pin "4") (pinfunction "E_4") (pintype "passive"))
    )
    (net (code "46") (name "Net-(U4-C)") (class "Default")
      (node (ref "R6") (pin "2") (pinfunction "2_2") (pintype "passive"))
      (node (ref "U4") (pin "5") (pinfunction "C_5") (pintype "passive"))
    )
    (net (code "47") (name "Net-(U4-K)") (class "Default")
      (node (ref "R12") (pin "2") (pinfunction "2_2") (pintype "passive"))
      (node (ref "U4") (pin "2") (pinfunction "K_2") (pintype "passive"))
    )
    (net (code "48") (name "Net-(U7-IN)") (class "Default")
      (node (ref "C28") (pin "1") (pinfunction "1_1") (pintype "passive"))
      (node (ref "L4") (pin "2") (pinfunction "2_2") (pintype "passive"))
      (node (ref "U7") (pin "1") (pinfunction "IN_1") (pintype "power_in"))
    )
    (net (code "49") (name "PGND") (class "Default")
      (node (ref "C18") (pin "2") (pinfunction "2_2") (pintype "passive"))
      (node (ref "C19") (pin "1") (pinfunction "1_1") (pintype "passive"))
      (node (ref "C20") (pin "2") (pinfunction "2_2") (pintype "passive"))
      (node (ref "C22") (pin "2") (pinfunction "2_2") (pintype "passive"))
      (node (ref "D10") (pin "1") (pinfunction "A_1") (pintype "passive"))
      (node (ref "P3") (pin "3") (pinfunction "3_3") (pintype "passive"))
      (node (ref "R20") (pin "2") (pinfunction "2_2") (pintype "passive"))
      (node (ref "TR1") (pin "5") (pinfunction "Sec3-_5") (pintype "passive"))
    )
    (net (code "50") (name "VBAT") (class "Default")
      (node (ref "D13") (pin "1") (pinfunction "A_1") (pintype "passive"))
      (node (ref "P3") (pin "1") (pinfunction "1_1") (pintype "passive"))
    )
    (net (code "51") (name "VCC") (class "Default")
      (node (ref "C29") (pin "1") (pinfunction "1_1") (pintype "passive"))
      (node (ref "C30") (pin "1") (pinfunction "1_1") (pintype "passive"))
      (node (ref "P1") (pin "4") (pinfunction "4_4") (pintype "passive"))
      (node (ref "U7") (pin "3") (pinfunction "OUT_3") (pintype "power_in"))
    )
    (net (code "52") (name "VDR") (class "Default")
      (node (ref "C23") (pin "1") (pinfunction "1_1") (pintype "passive"))
      (node (ref "C24") (pin "1") (pinfunction "1_1") (pintype "passive"))
      (node (ref "D11") (pin "2") (pinfunction "K_2") (pintype "passive"))
      (node (ref "D12") (pin "2") (pinfunction "K_2") (pintype "passive"))
      (node (ref "Q1") (pin "2") (pinfunction "C_2") (pintype "passive"))
      (node (ref "Q4") (pin "2") (pinfunction "C_2") (pintype "passive"))
    )
    (net (code "53") (name "VIN") (class "Default")
      (node (ref "C25") (pin "1") (pinfunction "1_1") (pintype "passive"))
      (node (ref "C26") (pin "1") (pinfunction "1_1") (pintype "passive"))
      (node (ref "D14") (pin "1") (pinfunction "A_1") (pintype "passive"))
      (node (ref "S1") (pin "2") (pinfunction "NO_2") (pintype "passive"))
      (node (ref "TR1") (pin "2") (pinfunction "Pri1-_2") (pintype "passive"))
      (node (ref "TR1") (pin "3") (pinfunction "Pri2+_3") (pintype "passive"))
    )
    (net (code "54") (name "unconnected-(U3-OSC_OUT-Pad4)") (class "Default")
      (node (ref "U3") (pin "4") (pinfunction "OSC_OUT_4") (pintype "output"))
    )
    (net (code "55") (name "unconnected-(U3-~{SYNC}-Pad3)") (class "Default")
      (node (ref "U3") (pin "3") (pinfunction "~{SYNC}_3") (pintype "input"))
    )
  )
)
